# INPUT_OUTPUT.net
KiCad netlist of a schematic drawn in Altium Designer
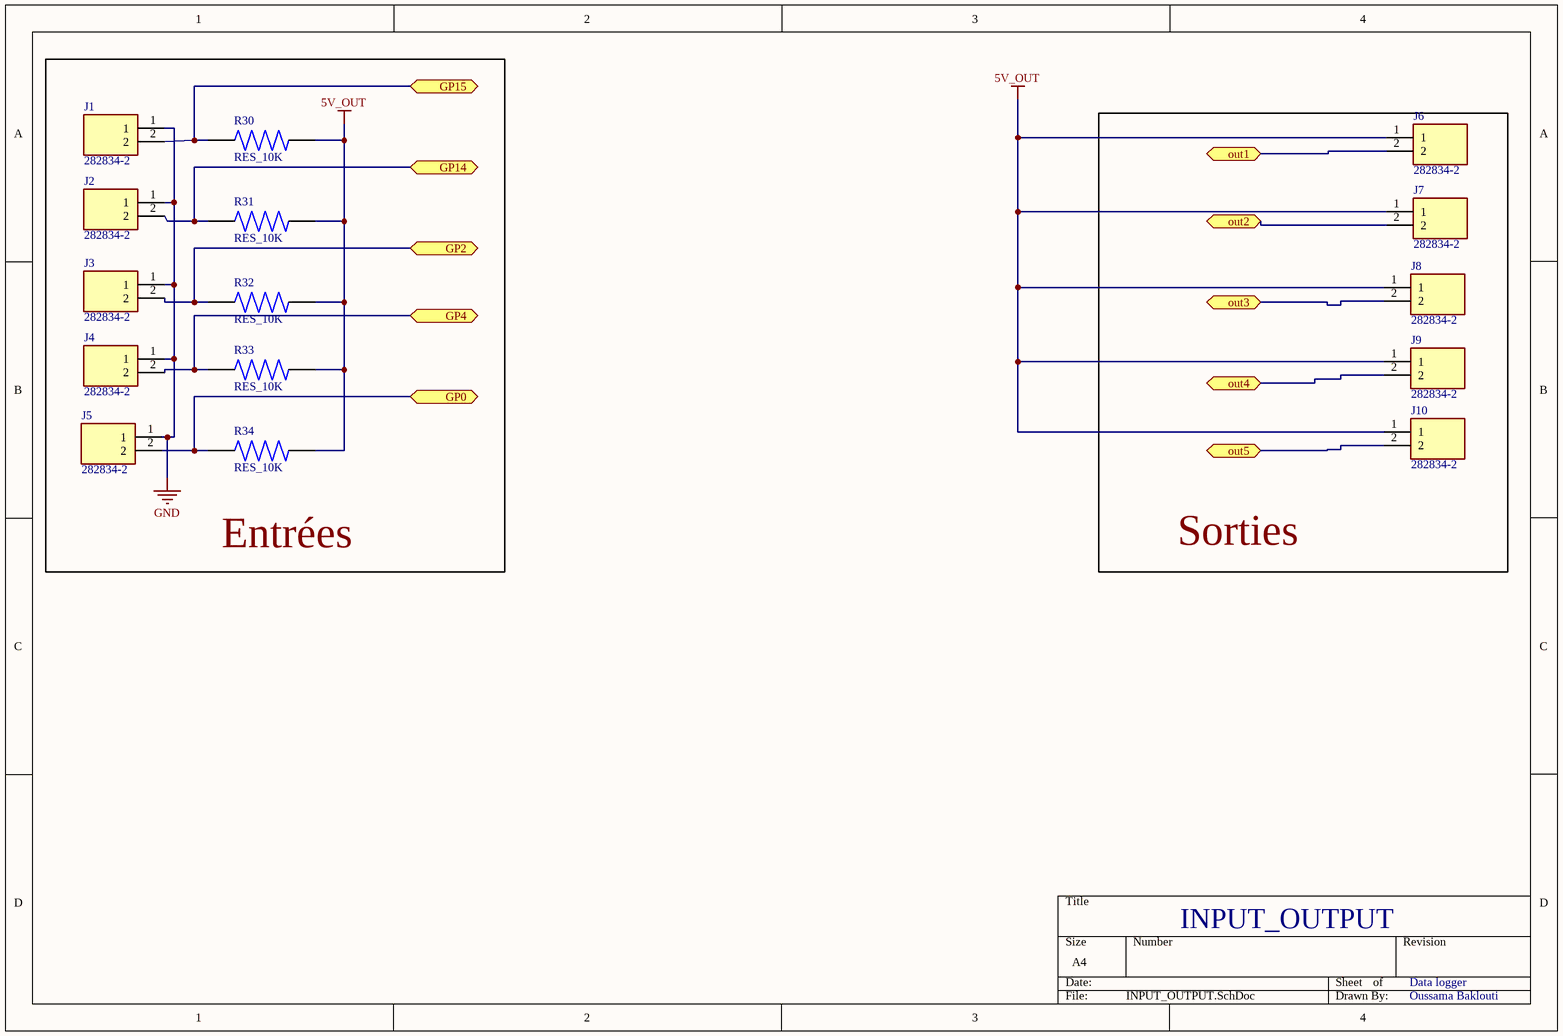
[diagram p0: INPUT_OUTPUT.SchDoc]

(export (version "E")
  (design (tool "Eeschema 10.0.6"))
  (components
    (comp (ref "J1")
      (value "282834-2")
      (footprint "282834-2")
      (description "Fixed Terminal Blocks 2P SIDE ENTRY 2.54mm")
      (fields (field (name "MFR") "TE Connectivity"))
      (libsource (lib "Data_logger") (part "282834-2"))
    )
    (comp (ref "J2")
      (value "282834-2")
      (footprint "282834-2")
      (description "Fixed Terminal Blocks 2P SIDE ENTRY 2.54mm")
      (fields (field (name "MFR") "TE Connectivity"))
      (libsource (lib "Data_logger") (part "282834-2"))
    )
    (comp (ref "J3")
      (value "282834-2")
      (footprint "282834-2")
      (description "Fixed Terminal Blocks 2P SIDE ENTRY 2.54mm")
      (fields (field (name "MFR") "TE Connectivity"))
      (libsource (lib "Data_logger") (part "282834-2"))
    )
    (comp (ref "J4")
      (value "282834-2")
      (footprint "282834-2")
      (description "Fixed Terminal Blocks 2P SIDE ENTRY 2.54mm")
      (fields (field (name "MFR") "TE Connectivity"))
      (libsource (lib "Data_logger") (part "282834-2"))
    )
    (comp (ref "J5")
      (value "282834-2")
      (footprint "282834-2")
      (description "Fixed Terminal Blocks 2P SIDE ENTRY 2.54mm")
      (fields (field (name "MFR") "TE Connectivity"))
      (libsource (lib "Data_logger") (part "282834-2"))
    )
    (comp (ref "J6")
      (value "282834-2")
      (footprint "282834-2")
      (description "Fixed Terminal Blocks 2P SIDE ENTRY 2.54mm")
      (fields (field (name "MFR") "TE Connectivity"))
      (libsource (lib "") (part "282834-2_1"))
    )
    (comp (ref "J7")
      (value "282834-2")
      (footprint "282834-2")
      (description "Fixed Terminal Blocks 2P SIDE ENTRY 2.54mm")
      (fields (field (name "MFR") "TE Connectivity"))
      (libsource (lib "") (part "282834-2_1"))
    )
    (comp (ref "J8")
      (value "282834-2")
      (footprint "282834-2")
      (description "Fixed Terminal Blocks 2P SIDE ENTRY 2.54mm")
      (fields (field (name "MFR") "TE Connectivity"))
      (libsource (lib "") (part "282834-2_1"))
    )
    (comp (ref "J9")
      (value "282834-2")
      (footprint "282834-2")
      (description "Fixed Terminal Blocks 2P SIDE ENTRY 2.54mm")
      (fields (field (name "MFR") "TE Connectivity"))
      (libsource (lib "") (part "282834-2_1"))
    )
    (comp (ref "J10")
      (value "282834-2")
      (footprint "282834-2")
      (description "Fixed Terminal Blocks 2P SIDE ENTRY 2.54mm")
      (fields (field (name "MFR") "TE Connectivity"))
      (libsource (lib "") (part "282834-2_1"))
    )
    (comp (ref "R30")
      (value "RES_10K")
      (footprint "RES_10k")
      (description "Thick Film Resistors - SMD ResHighPowerA 0805 10k 1% 1/2W TC100")
      (fields (field (name "MFR") "Bourns"))
      (libsource (lib "Data_logger") (part "RES_10K"))
    )
    (comp (ref "R31")
      (value "RES_10K")
      (footprint "RES_10k")
      (description "Thick Film Resistors - SMD ResHighPowerA 0805 10k 1% 1/2W TC100")
      (fields (field (name "MFR") "Bourns"))
      (libsource (lib "Data_logger") (part "RES_10K"))
    )
    (comp (ref "R32")
      (value "RES_10K")
      (footprint "RES_10k")
      (description "Thick Film Resistors - SMD ResHighPowerA 0805 10k 1% 1/2W TC100")
      (fields (field (name "MFR") "Bourns"))
      (libsource (lib "Data_logger") (part "RES_10K"))
    )
    (comp (ref "R33")
      (value "RES_10K")
      (footprint "RES_10k")
      (description "Thick Film Resistors - SMD ResHighPowerA 0805 10k 1% 1/2W TC100")
      (fields (field (name "MFR") "Bourns"))
      (libsource (lib "Data_logger") (part "RES_10K"))
    )
    (comp (ref "R34")
      (value "RES_10K")
      (footprint "RES_10k")
      (description "Thick Film Resistors - SMD ResHighPowerA 0805 10k 1% 1/2W TC100")
      (fields (field (name "MFR") "Bourns"))
      (libsource (lib "Data_logger") (part "RES_10K"))
    )
  )
  (nets
    (net (code "2") (name "/GP0") (class "Default")
      (node (ref "J5") (pin "2") (pinfunction "2_2") (pintype "passive"))
      (node (ref "R34") (pin "1") (pinfunction "1_1") (pintype "passive"))
    )
    (net (code "3") (name "/GP2") (class "Default")
      (node (ref "J3") (pin "2") (pinfunction "2_2") (pintype "passive"))
      (node (ref "R32") (pin "1") (pinfunction "1_1") (pintype "passive"))
    )
    (net (code "4") (name "/GP4") (class "Default")
      (node (ref "J4") (pin "2") (pinfunction "2_2") (pintype "passive"))
      (node (ref "R33") (pin "1") (pinfunction "1_1") (pintype "passive"))
    )
    (net (code "5") (name "/GP14") (class "Default")
      (node (ref "J2") (pin "2") (pinfunction "2_2") (pintype "passive"))
      (node (ref "R31") (pin "1") (pinfunction "1_1") (pintype "passive"))
    )
    (net (code "6") (name "/GP15") (class "Default")
      (node (ref "J1") (pin "2") (pinfunction "2_2") (pintype "passive"))
      (node (ref "R30") (pin "1") (pinfunction "1_1") (pintype "passive"))
    )
    (net (code "8") (name "/out1") (class "Default")
      (node (ref "J6") (pin "2") (pinfunction "2_2") (pintype "passive"))
    )
    (net (code "9") (name "/out2") (class "Default")
      (node (ref "J7") (pin "2") (pinfunction "2_2") (pintype "passive"))
    )
    (net (code "10") (name "/out3") (class "Default")
      (node (ref "J8") (pin "2") (pinfunction "2_2") (pintype "passive"))
    )
    (net (code "11") (name "/out4") (class "Default")
      (node (ref "J9") (pin "2") (pinfunction "2_2") (pintype "passive"))
    )
    (net (code "12") (name "/out5") (class "Default")
      (node (ref "J10") (pin "2") (pinfunction "2_2") (pintype "passive"))
    )
    (net (code "13") (name "5V_OUT") (class "Default")
      (node (ref "J10") (pin "1") (pinfunction "1_1") (pintype "passive"))
      (node (ref "J6") (pin "1") (pinfunction "1_1") (pintype "passive"))
      (node (ref "J7") (pin "1") (pinfunction "1_1") (pintype "passive"))
      (node (ref "J8") (pin "1") (pinfunction "1_1") (pintype "passive"))
      (node (ref "J9") (pin "1") (pinfunction "1_1") (pintype "passive"))
      (node (ref "R30") (pin "2") (pinfunction "2_2") (pintype "passive"))
      (node (ref "R31") (pin "2") (pinfunction "2_2") (pintype "passive"))
      (node (ref "R32") (pin "2") (pinfunction "2_2") (pintype "passive"))
      (node (ref "R33") (pin "2") (pinfunction "2_2") (pintype "passive"))
      (node (ref "R34") (pin "2") (pinfunction "2_2") (pintype "passive"))
    )
    (net (code "14") (name "GND") (class "Default")
      (node (ref "J1") (pin "1") (pinfunction "1_1") (pintype "passive"))
      (node (ref "J2") (pin "1") (pinfunction "1_1") (pintype "passive"))
      (node (ref "J3") (pin "1") (pinfunction "1_1") (pintype "passive"))
      (node (ref "J4") (pin "1") (pinfunction "1_1") (pintype "passive"))
      (node (ref "J5") (pin "1") (pinfunction "1_1") (pintype "passive"))
    )
  )
)
